# 2016.net
KiCad netlist of a schematic drawn in Altium Designer
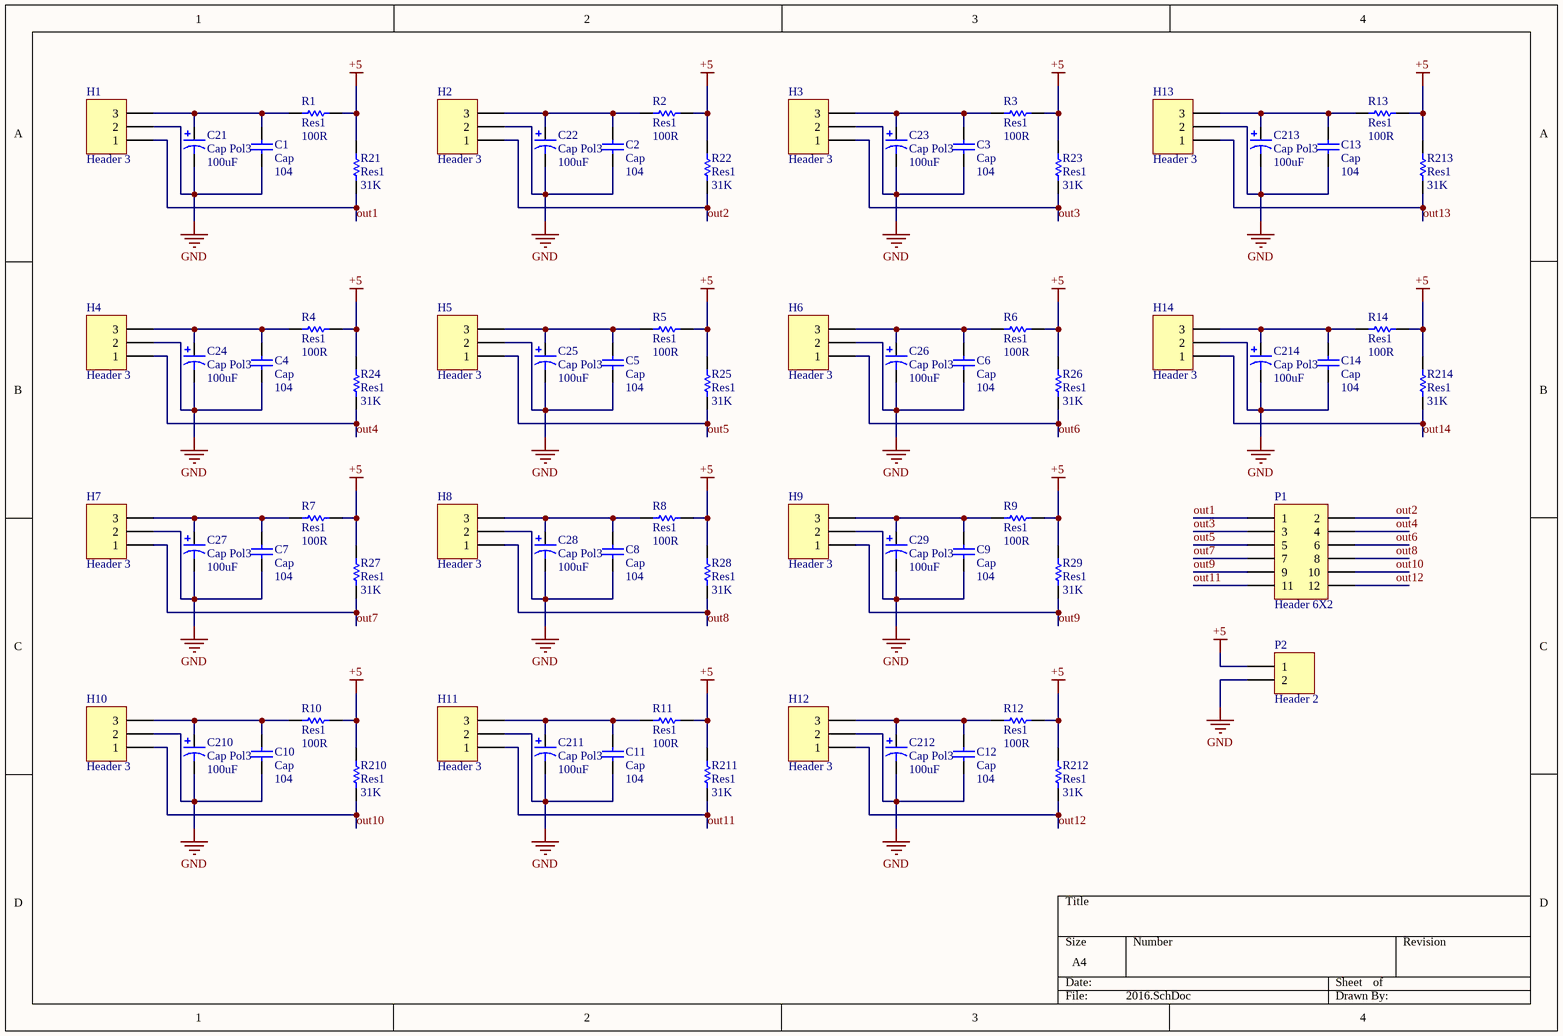
[diagram p0: 2016.SchDoc]

(export (version "E")
  (design (tool "Eeschema 10.0.6"))
  (components
    (comp (ref "C1")
      (value "Cap")
      (footprint "0805C")
      (description "Capacitor")
      (fields (field (name "ALTIUM_VALUE") "104") (field (name "PUBLISHER") "Altium Limited"))
      (libsource (lib "Miscellaneous Devices") (part "Cap"))
    )
    (comp (ref "C2")
      (value "Cap")
      (footprint "0805C")
      (description "Capacitor")
      (fields (field (name "ALTIUM_VALUE") "104") (field (name "PUBLISHER") "Altium Limited"))
      (libsource (lib "Miscellaneous Devices") (part "Cap"))
    )
    (comp (ref "C3")
      (value "Cap")
      (footprint "0805C")
      (description "Capacitor")
      (fields (field (name "ALTIUM_VALUE") "104") (field (name "PUBLISHER") "Altium Limited"))
      (libsource (lib "Miscellaneous Devices") (part "Cap"))
    )
    (comp (ref "C4")
      (value "Cap")
      (footprint "0805C")
      (description "Capacitor")
      (fields (field (name "ALTIUM_VALUE") "104") (field (name "PUBLISHER") "Altium Limited"))
      (libsource (lib "Miscellaneous Devices") (part "Cap"))
    )
    (comp (ref "C5")
      (value "Cap")
      (footprint "0805C")
      (description "Capacitor")
      (fields (field (name "ALTIUM_VALUE") "104") (field (name "PUBLISHER") "Altium Limited"))
      (libsource (lib "Miscellaneous Devices") (part "Cap"))
    )
    (comp (ref "C6")
      (value "Cap")
      (footprint "0805C")
      (description "Capacitor")
      (fields (field (name "ALTIUM_VALUE") "104") (field (name "PUBLISHER") "Altium Limited"))
      (libsource (lib "Miscellaneous Devices") (part "Cap"))
    )
    (comp (ref "C7")
      (value "Cap")
      (footprint "0805C")
      (description "Capacitor")
      (fields (field (name "ALTIUM_VALUE") "104") (field (name "PUBLISHER") "Altium Limited"))
      (libsource (lib "Miscellaneous Devices") (part "Cap"))
    )
    (comp (ref "C8")
      (value "Cap")
      (footprint "0805C")
      (description "Capacitor")
      (fields (field (name "ALTIUM_VALUE") "104") (field (name "PUBLISHER") "Altium Limited"))
      (libsource (lib "Miscellaneous Devices") (part "Cap"))
    )
    (comp (ref "C9")
      (value "Cap")
      (footprint "0805C")
      (description "Capacitor")
      (fields (field (name "ALTIUM_VALUE") "104") (field (name "PUBLISHER") "Altium Limited"))
      (libsource (lib "Miscellaneous Devices") (part "Cap"))
    )
    (comp (ref "C10")
      (value "Cap")
      (footprint "0805C")
      (description "Capacitor")
      (fields (field (name "ALTIUM_VALUE") "104") (field (name "PUBLISHER") "Altium Limited"))
      (libsource (lib "Miscellaneous Devices") (part "Cap"))
    )
    (comp (ref "C11")
      (value "Cap")
      (footprint "0805C")
      (description "Capacitor")
      (fields (field (name "ALTIUM_VALUE") "104") (field (name "PUBLISHER") "Altium Limited"))
      (libsource (lib "Miscellaneous Devices") (part "Cap"))
    )
    (comp (ref "C12")
      (value "Cap")
      (footprint "0805C")
      (description "Capacitor")
      (fields (field (name "ALTIUM_VALUE") "104") (field (name "PUBLISHER") "Altium Limited"))
      (libsource (lib "Miscellaneous Devices") (part "Cap"))
    )
    (comp (ref "C13")
      (value "Cap")
      (footprint "0805C")
      (description "Capacitor")
      (fields (field (name "ALTIUM_VALUE") "104") (field (name "PUBLISHER") "Altium Limited"))
      (libsource (lib "Miscellaneous Devices") (part "Cap"))
    )
    (comp (ref "C14")
      (value "Cap")
      (footprint "0805C")
      (description "Capacitor")
      (fields (field (name "ALTIUM_VALUE") "104") (field (name "PUBLISHER") "Altium Limited"))
      (libsource (lib "Miscellaneous Devices") (part "Cap"))
    )
    (comp (ref "C21")
      (value "Cap Pol3")
      (footprint "0805C")
      (description "Polarized Capacitor (Surface Mount)")
      (fields (field (name "ALTIUM_VALUE") "100uF") (field (name "PUBLISHER") "Altium Limited"))
      (libsource (lib "Miscellaneous Devices") (part "Cap Pol3"))
    )
    (comp (ref "C22")
      (value "Cap Pol3")
      (footprint "0805C")
      (description "Polarized Capacitor (Surface Mount)")
      (fields (field (name "ALTIUM_VALUE") "100uF") (field (name "PUBLISHER") "Altium Limited"))
      (libsource (lib "Miscellaneous Devices") (part "Cap Pol3"))
    )
    (comp (ref "C23")
      (value "Cap Pol3")
      (footprint "0805C")
      (description "Polarized Capacitor (Surface Mount)")
      (fields (field (name "ALTIUM_VALUE") "100uF") (field (name "PUBLISHER") "Altium Limited"))
      (libsource (lib "Miscellaneous Devices") (part "Cap Pol3"))
    )
    (comp (ref "C24")
      (value "Cap Pol3")
      (footprint "0805C")
      (description "Polarized Capacitor (Surface Mount)")
      (fields (field (name "ALTIUM_VALUE") "100uF") (field (name "PUBLISHER") "Altium Limited"))
      (libsource (lib "Miscellaneous Devices") (part "Cap Pol3"))
    )
    (comp (ref "C25")
      (value "Cap Pol3")
      (footprint "0805C")
      (description "Polarized Capacitor (Surface Mount)")
      (fields (field (name "ALTIUM_VALUE") "100uF") (field (name "PUBLISHER") "Altium Limited"))
      (libsource (lib "Miscellaneous Devices") (part "Cap Pol3"))
    )
    (comp (ref "C26")
      (value "Cap Pol3")
      (footprint "0805C")
      (description "Polarized Capacitor (Surface Mount)")
      (fields (field (name "ALTIUM_VALUE") "100uF") (field (name "PUBLISHER") "Altium Limited"))
      (libsource (lib "Miscellaneous Devices") (part "Cap Pol3"))
    )
    (comp (ref "C27")
      (value "Cap Pol3")
      (footprint "0805C")
      (description "Polarized Capacitor (Surface Mount)")
      (fields (field (name "ALTIUM_VALUE") "100uF") (field (name "PUBLISHER") "Altium Limited"))
      (libsource (lib "Miscellaneous Devices") (part "Cap Pol3"))
    )
    (comp (ref "C28")
      (value "Cap Pol3")
      (footprint "0805C")
      (description "Polarized Capacitor (Surface Mount)")
      (fields (field (name "ALTIUM_VALUE") "100uF") (field (name "PUBLISHER") "Altium Limited"))
      (libsource (lib "Miscellaneous Devices") (part "Cap Pol3"))
    )
    (comp (ref "C29")
      (value "Cap Pol3")
      (footprint "0805C")
      (description "Polarized Capacitor (Surface Mount)")
      (fields (field (name "ALTIUM_VALUE") "100uF") (field (name "PUBLISHER") "Altium Limited"))
      (libsource (lib "Miscellaneous Devices") (part "Cap Pol3"))
    )
    (comp (ref "C210")
      (value "Cap Pol3")
      (footprint "0805C")
      (description "Polarized Capacitor (Surface Mount)")
      (fields (field (name "ALTIUM_VALUE") "100uF") (field (name "PUBLISHER") "Altium Limited"))
      (libsource (lib "Miscellaneous Devices") (part "Cap Pol3"))
    )
    (comp (ref "C211")
      (value "Cap Pol3")
      (footprint "0805C")
      (description "Polarized Capacitor (Surface Mount)")
      (fields (field (name "ALTIUM_VALUE") "100uF") (field (name "PUBLISHER") "Altium Limited"))
      (libsource (lib "Miscellaneous Devices") (part "Cap Pol3"))
    )
    (comp (ref "C212")
      (value "Cap Pol3")
      (footprint "0805C")
      (description "Polarized Capacitor (Surface Mount)")
      (fields (field (name "ALTIUM_VALUE") "100uF") (field (name "PUBLISHER") "Altium Limited"))
      (libsource (lib "Miscellaneous Devices") (part "Cap Pol3"))
    )
    (comp (ref "C213")
      (value "Cap Pol3")
      (footprint "0805C")
      (description "Polarized Capacitor (Surface Mount)")
      (fields (field (name "ALTIUM_VALUE") "100uF") (field (name "PUBLISHER") "Altium Limited"))
      (libsource (lib "Miscellaneous Devices") (part "Cap Pol3"))
    )
    (comp (ref "C214")
      (value "Cap Pol3")
      (footprint "0805C")
      (description "Polarized Capacitor (Surface Mount)")
      (fields (field (name "ALTIUM_VALUE") "100uF") (field (name "PUBLISHER") "Altium Limited"))
      (libsource (lib "Miscellaneous Devices") (part "Cap Pol3"))
    )
    (comp (ref "H1")
      (value "Header 3")
      (footprint "HDR1X3")
      (description "Header, 3-Pin")
      (fields (field (name "PUBLISHER") "Altium Limited"))
      (libsource (lib "Miscellaneous Connectors") (part "Header 3"))
    )
    (comp (ref "H2")
      (value "Header 3")
      (footprint "HDR1X3")
      (description "Header, 3-Pin")
      (fields (field (name "PUBLISHER") "Altium Limited"))
      (libsource (lib "Miscellaneous Connectors") (part "Header 3"))
    )
    (comp (ref "H3")
      (value "Header 3")
      (footprint "HDR1X3")
      (description "Header, 3-Pin")
      (fields (field (name "PUBLISHER") "Altium Limited"))
      (libsource (lib "Miscellaneous Connectors") (part "Header 3"))
    )
    (comp (ref "H4")
      (value "Header 3")
      (footprint "HDR1X3")
      (description "Header, 3-Pin")
      (fields (field (name "PUBLISHER") "Altium Limited"))
      (libsource (lib "Miscellaneous Connectors") (part "Header 3"))
    )
    (comp (ref "H5")
      (value "Header 3")
      (footprint "HDR1X3")
      (description "Header, 3-Pin")
      (fields (field (name "PUBLISHER") "Altium Limited"))
      (libsource (lib "Miscellaneous Connectors") (part "Header 3"))
    )
    (comp (ref "H6")
      (value "Header 3")
      (footprint "HDR1X3")
      (description "Header, 3-Pin")
      (fields (field (name "PUBLISHER") "Altium Limited"))
      (libsource (lib "Miscellaneous Connectors") (part "Header 3"))
    )
    (comp (ref "H7")
      (value "Header 3")
      (footprint "HDR1X3")
      (description "Header, 3-Pin")
      (fields (field (name "PUBLISHER") "Altium Limited"))
      (libsource (lib "Miscellaneous Connectors") (part "Header 3"))
    )
    (comp (ref "H8")
      (value "Header 3")
      (footprint "HDR1X3")
      (description "Header, 3-Pin")
      (fields (field (name "PUBLISHER") "Altium Limited"))
      (libsource (lib "Miscellaneous Connectors") (part "Header 3"))
    )
    (comp (ref "H9")
      (value "Header 3")
      (footprint "HDR1X3")
      (description "Header, 3-Pin")
      (fields (field (name "PUBLISHER") "Altium Limited"))
      (libsource (lib "Miscellaneous Connectors") (part "Header 3"))
    )
    (comp (ref "H10")
      (value "Header 3")
      (footprint "HDR1X3")
      (description "Header, 3-Pin")
      (fields (field (name "PUBLISHER") "Altium Limited"))
      (libsource (lib "Miscellaneous Connectors") (part "Header 3"))
    )
    (comp (ref "H11")
      (value "Header 3")
      (footprint "HDR1X3")
      (description "Header, 3-Pin")
      (fields (field (name "PUBLISHER") "Altium Limited"))
      (libsource (lib "Miscellaneous Connectors") (part "Header 3"))
    )
    (comp (ref "H12")
      (value "Header 3")
      (footprint "HDR1X3")
      (description "Header, 3-Pin")
      (fields (field (name "PUBLISHER") "Altium Limited"))
      (libsource (lib "Miscellaneous Connectors") (part "Header 3"))
    )
    (comp (ref "H13")
      (value "Header 3")
      (footprint "HDR1X3")
      (description "Header, 3-Pin")
      (fields (field (name "PUBLISHER") "Altium Limited"))
      (libsource (lib "Miscellaneous Connectors") (part "Header 3"))
    )
    (comp (ref "H14")
      (value "Header 3")
      (footprint "HDR1X3")
      (description "Header, 3-Pin")
      (fields (field (name "PUBLISHER") "Altium Limited"))
      (libsource (lib "Miscellaneous Connectors") (part "Header 3"))
    )
    (comp (ref "P1")
      (value "Header 6X2")
      (footprint "HDR2X6")
      (description "Header, 6-Pin, Dual row")
      (fields (field (name "PUBLISHER") "Altium Limited"))
      (libsource (lib "Miscellaneous Connectors") (part "Header 6X2"))
    )
    (comp (ref "P2")
      (value "Header 2")
      (footprint "HDR1X2")
      (description "Header, 2-Pin")
      (fields (field (name "PUBLISHER") "Altium Limited"))
      (libsource (lib "Miscellaneous Connectors") (part "Header 2"))
    )
    (comp (ref "R1")
      (value "Res1")
      (footprint "0805R")
      (description "Resistor")
      (fields (field (name "ALTIUM_VALUE") "100R") (field (name "PUBLISHER") "Altium Limited"))
      (libsource (lib "Miscellaneous Devices") (part "Res1"))
    )
    (comp (ref "R2")
      (value "Res1")
      (footprint "0805R")
      (description "Resistor")
      (fields (field (name "ALTIUM_VALUE") "100R") (field (name "PUBLISHER") "Altium Limited"))
      (libsource (lib "Miscellaneous Devices") (part "Res1"))
    )
    (comp (ref "R3")
      (value "Res1")
      (footprint "0805R")
      (description "Resistor")
      (fields (field (name "ALTIUM_VALUE") "100R") (field (name "PUBLISHER") "Altium Limited"))
      (libsource (lib "Miscellaneous Devices") (part "Res1"))
    )
    (comp (ref "R4")
      (value "Res1")
      (footprint "0805R")
      (description "Resistor")
      (fields (field (name "ALTIUM_VALUE") "100R") (field (name "PUBLISHER") "Altium Limited"))
      (libsource (lib "Miscellaneous Devices") (part "Res1"))
    )
    (comp (ref "R5")
      (value "Res1")
      (footprint "0805R")
      (description "Resistor")
      (fields (field (name "ALTIUM_VALUE") "100R") (field (name "PUBLISHER") "Altium Limited"))
      (libsource (lib "Miscellaneous Devices") (part "Res1"))
    )
    (comp (ref "R6")
      (value "Res1")
      (footprint "0805R")
      (description "Resistor")
      (fields (field (name "ALTIUM_VALUE") "100R") (field (name "PUBLISHER") "Altium Limited"))
      (libsource (lib "Miscellaneous Devices") (part "Res1"))
    )
    (comp (ref "R7")
      (value "Res1")
      (footprint "0805R")
      (description "Resistor")
      (fields (field (name "ALTIUM_VALUE") "100R") (field (name "PUBLISHER") "Altium Limited"))
      (libsource (lib "Miscellaneous Devices") (part "Res1"))
    )
    (comp (ref "R8")
      (value "Res1")
      (footprint "0805R")
      (description "Resistor")
      (fields (field (name "ALTIUM_VALUE") "100R") (field (name "PUBLISHER") "Altium Limited"))
      (libsource (lib "Miscellaneous Devices") (part "Res1"))
    )
    (comp (ref "R9")
      (value "Res1")
      (footprint "0805R")
      (description "Resistor")
      (fields (field (name "ALTIUM_VALUE") "100R") (field (name "PUBLISHER") "Altium Limited"))
      (libsource (lib "Miscellaneous Devices") (part "Res1"))
    )
    (comp (ref "R10")
      (value "Res1")
      (footprint "0805R")
      (description "Resistor")
      (fields (field (name "ALTIUM_VALUE") "100R") (field (name "PUBLISHER") "Altium Limited"))
      (libsource (lib "Miscellaneous Devices") (part "Res1"))
    )
    (comp (ref "R11")
      (value "Res1")
      (footprint "0805R")
      (description "Resistor")
      (fields (field (name "ALTIUM_VALUE") "100R") (field (name "PUBLISHER") "Altium Limited"))
      (libsource (lib "Miscellaneous Devices") (part "Res1"))
    )
    (comp (ref "R12")
      (value "Res1")
      (footprint "0805R")
      (description "Resistor")
      (fields (field (name "ALTIUM_VALUE") "100R") (field (name "PUBLISHER") "Altium Limited"))
      (libsource (lib "Miscellaneous Devices") (part "Res1"))
    )
    (comp (ref "R13")
      (value "Res1")
      (footprint "0805R")
      (description "Resistor")
      (fields (field (name "ALTIUM_VALUE") "100R") (field (name "PUBLISHER") "Altium Limited"))
      (libsource (lib "Miscellaneous Devices") (part "Res1"))
    )
    (comp (ref "R14")
      (value "Res1")
      (footprint "0805R")
      (description "Resistor")
      (fields (field (name "ALTIUM_VALUE") "100R") (field (name "PUBLISHER") "Altium Limited"))
      (libsource (lib "Miscellaneous Devices") (part "Res1"))
    )
    (comp (ref "R21")
      (value "Res1")
      (footprint "0805R")
      (description "Resistor")
      (fields (field (name "ALTIUM_VALUE") "31K") (field (name "PUBLISHER") "Altium Limited"))
      (libsource (lib "Miscellaneous Devices") (part "Res1"))
    )
    (comp (ref "R22")
      (value "Res1")
      (footprint "0805R")
      (description "Resistor")
      (fields (field (name "ALTIUM_VALUE") "31K") (field (name "PUBLISHER") "Altium Limited"))
      (libsource (lib "Miscellaneous Devices") (part "Res1"))
    )
    (comp (ref "R23")
      (value "Res1")
      (footprint "0805R")
      (description "Resistor")
      (fields (field (name "ALTIUM_VALUE") "31K") (field (name "PUBLISHER") "Altium Limited"))
      (libsource (lib "Miscellaneous Devices") (part "Res1"))
    )
    (comp (ref "R24")
      (value "Res1")
      (footprint "0805R")
      (description "Resistor")
      (fields (field (name "ALTIUM_VALUE") "31K") (field (name "PUBLISHER") "Altium Limited"))
      (libsource (lib "Miscellaneous Devices") (part "Res1"))
    )
    (comp (ref "R25")
      (value "Res1")
      (footprint "0805R")
      (description "Resistor")
      (fields (field (name "ALTIUM_VALUE") "31K") (field (name "PUBLISHER") "Altium Limited"))
      (libsource (lib "Miscellaneous Devices") (part "Res1"))
    )
    (comp (ref "R26")
      (value "Res1")
      (footprint "0805R")
      (description "Resistor")
      (fields (field (name "ALTIUM_VALUE") "31K") (field (name "PUBLISHER") "Altium Limited"))
      (libsource (lib "Miscellaneous Devices") (part "Res1"))
    )
    (comp (ref "R27")
      (value "Res1")
      (footprint "0805R")
      (description "Resistor")
      (fields (field (name "ALTIUM_VALUE") "31K") (field (name "PUBLISHER") "Altium Limited"))
      (libsource (lib "Miscellaneous Devices") (part "Res1"))
    )
    (comp (ref "R28")
      (value "Res1")
      (footprint "0805R")
      (description "Resistor")
      (fields (field (name "ALTIUM_VALUE") "31K") (field (name "PUBLISHER") "Altium Limited"))
      (libsource (lib "Miscellaneous Devices") (part "Res1"))
    )
    (comp (ref "R29")
      (value "Res1")
      (footprint "0805R")
      (description "Resistor")
      (fields (field (name "ALTIUM_VALUE") "31K") (field (name "PUBLISHER") "Altium Limited"))
      (libsource (lib "Miscellaneous Devices") (part "Res1"))
    )
    (comp (ref "R210")
      (value "Res1")
      (footprint "0805R")
      (description "Resistor")
      (fields (field (name "ALTIUM_VALUE") "31K") (field (name "PUBLISHER") "Altium Limited"))
      (libsource (lib "Miscellaneous Devices") (part "Res1"))
    )
    (comp (ref "R211")
      (value "Res1")
      (footprint "0805R")
      (description "Resistor")
      (fields (field (name "ALTIUM_VALUE") "31K") (field (name "PUBLISHER") "Altium Limited"))
      (libsource (lib "Miscellaneous Devices") (part "Res1"))
    )
    (comp (ref "R212")
      (value "Res1")
      (footprint "0805R")
      (description "Resistor")
      (fields (field (name "ALTIUM_VALUE") "31K") (field (name "PUBLISHER") "Altium Limited"))
      (libsource (lib "Miscellaneous Devices") (part "Res1"))
    )
    (comp (ref "R213")
      (value "Res1")
      (footprint "0805R")
      (description "Resistor")
      (fields (field (name "ALTIUM_VALUE") "31K") (field (name "PUBLISHER") "Altium Limited"))
      (libsource (lib "Miscellaneous Devices") (part "Res1"))
    )
    (comp (ref "R214")
      (value "Res1")
      (footprint "0805R")
      (description "Resistor")
      (fields (field (name "ALTIUM_VALUE") "31K") (field (name "PUBLISHER") "Altium Limited"))
      (libsource (lib "Miscellaneous Devices") (part "Res1"))
    )
  )
  (nets
    (net (code "1") (name "+5") (class "Default")
      (node (ref "P2") (pin "1") (pinfunction "1_1") (pintype "passive"))
      (node (ref "R1") (pin "2") (pinfunction "2_2") (pintype "passive"))
      (node (ref "R10") (pin "2") (pinfunction "2_2") (pintype "passive"))
      (node (ref "R11") (pin "2") (pinfunction "2_2") (pintype "passive"))
      (node (ref "R12") (pin "2") (pinfunction "2_2") (pintype "passive"))
      (node (ref "R13") (pin "2") (pinfunction "2_2") (pintype "passive"))
      (node (ref "R14") (pin "2") (pinfunction "2_2") (pintype "passive"))
      (node (ref "R2") (pin "2") (pinfunction "2_2") (pintype "passive"))
      (node (ref "R21") (pin "2") (pinfunction "2_2") (pintype "passive"))
      (node (ref "R210") (pin "2") (pinfunction "2_2") (pintype "passive"))
      (node (ref "R211") (pin "2") (pinfunction "2_2") (pintype "passive"))
      (node (ref "R212") (pin "2") (pinfunction "2_2") (pintype "passive"))
      (node (ref "R213") (pin "2") (pinfunction "2_2") (pintype "passive"))
      (node (ref "R214") (pin "2") (pinfunction "2_2") (pintype "passive"))
      (node (ref "R22") (pin "2") (pinfunction "2_2") (pintype "passive"))
      (node (ref "R23") (pin "2") (pinfunction "2_2") (pintype "passive"))
      (node (ref "R24") (pin "2") (pinfunction "2_2") (pintype "passive"))
      (node (ref "R25") (pin "2") (pinfunction "2_2") (pintype "passive"))
      (node (ref "R26") (pin "2") (pinfunction "2_2") (pintype "passive"))
      (node (ref "R27") (pin "2") (pinfunction "2_2") (pintype "passive"))
      (node (ref "R28") (pin "2") (pinfunction "2_2") (pintype "passive"))
      (node (ref "R29") (pin "2") (pinfunction "2_2") (pintype "passive"))
      (node (ref "R3") (pin "2") (pinfunction "2_2") (pintype "passive"))
      (node (ref "R4") (pin "2") (pinfunction "2_2") (pintype "passive"))
      (node (ref "R5") (pin "2") (pinfunction "2_2") (pintype "passive"))
      (node (ref "R6") (pin "2") (pinfunction "2_2") (pintype "passive"))
      (node (ref "R7") (pin "2") (pinfunction "2_2") (pintype "passive"))
      (node (ref "R8") (pin "2") (pinfunction "2_2") (pintype "passive"))
      (node (ref "R9") (pin "2") (pinfunction "2_2") (pintype "passive"))
    )
    (net (code "2") (name "/out1") (class "Default")
      (node (ref "H1") (pin "1") (pinfunction "1_1") (pintype "passive"))
      (node (ref "P1") (pin "1") (pinfunction "1_1") (pintype "passive"))
      (node (ref "R21") (pin "1") (pinfunction "1_1") (pintype "passive"))
    )
    (net (code "3") (name "/out2") (class "Default")
      (node (ref "H2") (pin "1") (pinfunction "1_1") (pintype "passive"))
      (node (ref "P1") (pin "2") (pinfunction "2_2") (pintype "passive"))
      (node (ref "R22") (pin "1") (pinfunction "1_1") (pintype "passive"))
    )
    (net (code "4") (name "/out3") (class "Default")
      (node (ref "H3") (pin "1") (pinfunction "1_1") (pintype "passive"))
      (node (ref "P1") (pin "3") (pinfunction "3_3") (pintype "passive"))
      (node (ref "R23") (pin "1") (pinfunction "1_1") (pintype "passive"))
    )
    (net (code "5") (name "/out4") (class "Default")
      (node (ref "H4") (pin "1") (pinfunction "1_1") (pintype "passive"))
      (node (ref "P1") (pin "4") (pinfunction "4_4") (pintype "passive"))
      (node (ref "R24") (pin "1") (pinfunction "1_1") (pintype "passive"))
    )
    (net (code "6") (name "/out5") (class "Default")
      (node (ref "H5") (pin "1") (pinfunction "1_1") (pintype "passive"))
      (node (ref "P1") (pin "5") (pinfunction "5_5") (pintype "passive"))
      (node (ref "R25") (pin "1") (pinfunction "1_1") (pintype "passive"))
    )
    (net (code "7") (name "/out6") (class "Default")
      (node (ref "H6") (pin "1") (pinfunction "1_1") (pintype "passive"))
      (node (ref "P1") (pin "6") (pinfunction "6_6") (pintype "passive"))
      (node (ref "R26") (pin "1") (pinfunction "1_1") (pintype "passive"))
    )
    (net (code "8") (name "/out7") (class "Default")
      (node (ref "H7") (pin "1") (pinfunction "1_1") (pintype "passive"))
      (node (ref "P1") (pin "7") (pinfunction "7_7") (pintype "passive"))
      (node (ref "R27") (pin "1") (pinfunction "1_1") (pintype "passive"))
    )
    (net (code "9") (name "/out8") (class "Default")
      (node (ref "H8") (pin "1") (pinfunction "1_1") (pintype "passive"))
      (node (ref "P1") (pin "8") (pinfunction "8_8") (pintype "passive"))
      (node (ref "R28") (pin "1") (pinfunction "1_1") (pintype "passive"))
    )
    (net (code "10") (name "/out9") (class "Default")
      (node (ref "H9") (pin "1") (pinfunction "1_1") (pintype "passive"))
      (node (ref "P1") (pin "9") (pinfunction "9_9") (pintype "passive"))
      (node (ref "R29") (pin "1") (pinfunction "1_1") (pintype "passive"))
    )
    (net (code "11") (name "/out10") (class "Default")
      (node (ref "H10") (pin "1") (pinfunction "1_1") (pintype "passive"))
      (node (ref "P1") (pin "10") (pinfunction "10_10") (pintype "passive"))
      (node (ref "R210") (pin "1") (pinfunction "1_1") (pintype "passive"))
    )
    (net (code "12") (name "/out11") (class "Default")
      (node (ref "H11") (pin "1") (pinfunction "1_1") (pintype "passive"))
      (node (ref "P1") (pin "11") (pinfunction "11_11") (pintype "passive"))
      (node (ref "R211") (pin "1") (pinfunction "1_1") (pintype "passive"))
    )
    (net (code "13") (name "/out12") (class "Default")
      (node (ref "H12") (pin "1") (pinfunction "1_1") (pintype "passive"))
      (node (ref "P1") (pin "12") (pinfunction "12_12") (pintype "passive"))
      (node (ref "R212") (pin "1") (pinfunction "1_1") (pintype "passive"))
    )
    (net (code "14") (name "/out13") (class "Default")
      (node (ref "H13") (pin "1") (pinfunction "1_1") (pintype "passive"))
      (node (ref "R213") (pin "1") (pinfunction "1_1") (pintype "passive"))
    )
    (net (code "15") (name "/out14") (class "Default")
      (node (ref "H14") (pin "1") (pinfunction "1_1") (pintype "passive"))
      (node (ref "R214") (pin "1") (pinfunction "1_1") (pintype "passive"))
    )
    (net (code "16") (name "GND") (class "Default")
      (node (ref "C1") (pin "1") (pinfunction "1_1") (pintype "passive"))
      (node (ref "C10") (pin "1") (pinfunction "1_1") (pintype "passive"))
      (node (ref "C11") (pin "1") (pinfunction "1_1") (pintype "passive"))
      (node (ref "C12") (pin "1") (pinfunction "1_1") (pintype "passive"))
      (node (ref "C13") (pin "1") (pinfunction "1_1") (pintype "passive"))
      (node (ref "C14") (pin "1") (pinfunction "1_1") (pintype "passive"))
      (node (ref "C2") (pin "1") (pinfunction "1_1") (pintype "passive"))
      (node (ref "C21") (pin "2") (pinfunction "2_2") (pintype "passive"))
      (node (ref "C210") (pin "2") (pinfunction "2_2") (pintype "passive"))
      (node (ref "C211") (pin "2") (pinfunction "2_2") (pintype "passive"))
      (node (ref "C212") (pin "2") (pinfunction "2_2") (pintype "passive"))
      (node (ref "C213") (pin "2") (pinfunction "2_2") (pintype "passive"))
      (node (ref "C214") (pin "2") (pinfunction "2_2") (pintype "passive"))
      (node (ref "C22") (pin "2") (pinfunction "2_2") (pintype "passive"))
      (node (ref "C23") (pin "2") (pinfunction "2_2") (pintype "passive"))
      (node (ref "C24") (pin "2") (pinfunction "2_2") (pintype "passive"))
      (node (ref "C25") (pin "2") (pinfunction "2_2") (pintype "passive"))
      (node (ref "C26") (pin "2") (pinfunction "2_2") (pintype "passive"))
      (node (ref "C27") (pin "2") (pinfunction "2_2") (pintype "passive"))
      (node (ref "C28") (pin "2") (pinfunction "2_2") (pintype "passive"))
      (node (ref "C29") (pin "2") (pinfunction "2_2") (pintype "passive"))
      (node (ref "C3") (pin "1") (pinfunction "1_1") (pintype "passive"))
      (node (ref "C4") (pin "1") (pinfunction "1_1") (pintype "passive"))
      (node (ref "C5") (pin "1") (pinfunction "1_1") (pintype "passive"))
      (node (ref "C6") (pin "1") (pinfunction "1_1") (pintype "passive"))
      (node (ref "C7") (pin "1") (pinfunction "1_1") (pintype "passive"))
      (node (ref "C8") (pin "1") (pinfunction "1_1") (pintype "passive"))
      (node (ref "C9") (pin "1") (pinfunction "1_1") (pintype "passive"))
      (node (ref "H1") (pin "2") (pinfunction "2_2") (pintype "passive"))
      (node (ref "H10") (pin "2") (pinfunction "2_2") (pintype "passive"))
      (node (ref "H11") (pin "2") (pinfunction "2_2") (pintype "passive"))
      (node (ref "H12") (pin "2") (pinfunction "2_2") (pintype "passive"))
      (node (ref "H13") (pin "2") (pinfunction "2_2") (pintype "passive"))
      (node (ref "H14") (pin "2") (pinfunction "2_2") (pintype "passive"))
      (node (ref "H2") (pin "2") (pinfunction "2_2") (pintype "passive"))
      (node (ref "H3") (pin "2") (pinfunction "2_2") (pintype "passive"))
      (node (ref "H4") (pin "2") (pinfunction "2_2") (pintype "passive"))
      (node (ref "H5") (pin "2") (pinfunction "2_2") (pintype "passive"))
      (node (ref "H6") (pin "2") (pinfunction "2_2") (pintype "passive"))
      (node (ref "H7") (pin "2") (pinfunction "2_2") (pintype "passive"))
      (node (ref "H8") (pin "2") (pinfunction "2_2") (pintype "passive"))
      (node (ref "H9") (pin "2") (pinfunction "2_2") (pintype "passive"))
      (node (ref "P2") (pin "2") (pinfunction "2_2") (pintype "passive"))
    )
    (net (code "17") (name "Net-(C1-Pad2)") (class "Default")
      (node (ref "C1") (pin "2") (pinfunction "2_2") (pintype "passive"))
      (node (ref "C21") (pin "1") (pinfunction "1_1") (pintype "passive"))
      (node (ref "H1") (pin "3") (pinfunction "3_3") (pintype "passive"))
      (node (ref "R1") (pin "1") (pinfunction "1_1") (pintype "passive"))
    )
    (net (code "18") (name "Net-(C2-Pad2)") (class "Default")
      (node (ref "C2") (pin "2") (pinfunction "2_2") (pintype "passive"))
      (node (ref "C22") (pin "1") (pinfunction "1_1") (pintype "passive"))
      (node (ref "H2") (pin "3") (pinfunction "3_3") (pintype "passive"))
      (node (ref "R2") (pin "1") (pinfunction "1_1") (pintype "passive"))
    )
    (net (code "19") (name "Net-(C10-Pad2)") (class "Default")
      (node (ref "C10") (pin "2") (pinfunction "2_2") (pintype "passive"))
      (node (ref "C210") (pin "1") (pinfunction "1_1") (pintype "passive"))
      (node (ref "H10") (pin "3") (pinfunction "3_3") (pintype "passive"))
      (node (ref "R10") (pin "1") (pinfunction "1_1") (pintype "passive"))
    )
    (net (code "20") (name "Net-(C11-Pad2)") (class "Default")
      (node (ref "C11") (pin "2") (pinfunction "2_2") (pintype "passive"))
      (node (ref "C211") (pin "1") (pinfunction "1_1") (pintype "passive"))
      (node (ref "H11") (pin "3") (pinfunction "3_3") (pintype "passive"))
      (node (ref "R11") (pin "1") (pinfunction "1_1") (pintype "passive"))
    )
    (net (code "21") (name "Net-(C12-Pad2)") (class "Default")
      (node (ref "C12") (pin "2") (pinfunction "2_2") (pintype "passive"))
      (node (ref "C212") (pin "1") (pinfunction "1_1") (pintype "passive"))
      (node (ref "H12") (pin "3") (pinfunction "3_3") (pintype "passive"))
      (node (ref "R12") (pin "1") (pinfunction "1_1") (pintype "passive"))
    )
    (net (code "22") (name "Net-(C13-Pad2)") (class "Default")
      (node (ref "C13") (pin "2") (pinfunction "2_2") (pintype "passive"))
      (node (ref "C213") (pin "1") (pinfunction "1_1") (pintype "passive"))
      (node (ref "H13") (pin "3") (pinfunction "3_3") (pintype "passive"))
      (node (ref "R13") (pin "1") (pinfunction "1_1") (pintype "passive"))
    )
    (net (code "23") (name "Net-(C14-Pad2)") (class "Default")
      (node (ref "C14") (pin "2") (pinfunction "2_2") (pintype "passive"))
      (node (ref "C214") (pin "1") (pinfunction "1_1") (pintype "passive"))
      (node (ref "H14") (pin "3") (pinfunction "3_3") (pintype "passive"))
      (node (ref "R14") (pin "1") (pinfunction "1_1") (pintype "passive"))
    )
    (net (code "24") (name "Net-(C23-Pad1)") (class "Default")
      (node (ref "C23") (pin "1") (pinfunction "1_1") (pintype "passive"))
      (node (ref "C3") (pin "2") (pinfunction "2_2") (pintype "passive"))
      (node (ref "H3") (pin "3") (pinfunction "3_3") (pintype "passive"))
      (node (ref "R3") (pin "1") (pinfunction "1_1") (pintype "passive"))
    )
    (net (code "25") (name "Net-(C24-Pad1)") (class "Default")
      (node (ref "C24") (pin "1") (pinfunction "1_1") (pintype "passive"))
      (node (ref "C4") (pin "2") (pinfunction "2_2") (pintype "passive"))
      (node (ref "H4") (pin "3") (pinfunction "3_3") (pintype "passive"))
      (node (ref "R4") (pin "1") (pinfunction "1_1") (pintype "passive"))
    )
    (net (code "26") (name "Net-(C25-Pad1)") (class "Default")
      (node (ref "C25") (pin "1") (pinfunction "1_1") (pintype "passive"))
      (node (ref "C5") (pin "2") (pinfunction "2_2") (pintype "passive"))
      (node (ref "H5") (pin "3") (pinfunction "3_3") (pintype "passive"))
      (node (ref "R5") (pin "1") (pinfunction "1_1") (pintype "passive"))
    )
    (net (code "27") (name "Net-(C26-Pad1)") (class "Default")
      (node (ref "C26") (pin "1") (pinfunction "1_1") (pintype "passive"))
      (node (ref "C6") (pin "2") (pinfunction "2_2") (pintype "passive"))
      (node (ref "H6") (pin "3") (pinfunction "3_3") (pintype "passive"))
      (node (ref "R6") (pin "1") (pinfunction "1_1") (pintype "passive"))
    )
    (net (code "28") (name "Net-(C27-Pad1)") (class "Default")
      (node (ref "C27") (pin "1") (pinfunction "1_1") (pintype "passive"))
      (node (ref "C7") (pin "2") (pinfunction "2_2") (pintype "passive"))
      (node (ref "H7") (pin "3") (pinfunction "3_3") (pintype "passive"))
      (node (ref "R7") (pin "1") (pinfunction "1_1") (pintype "passive"))
    )
    (net (code "29") (name "Net-(C28-Pad1)") (class "Default")
      (node (ref "C28") (pin "1") (pinfunction "1_1") (pintype "passive"))
      (node (ref "C8") (pin "2") (pinfunction "2_2") (pintype "passive"))
      (node (ref "H8") (pin "3") (pinfunction "3_3") (pintype "passive"))
      (node (ref "R8") (pin "1") (pinfunction "1_1") (pintype "passive"))
    )
    (net (code "30") (name "Net-(C29-Pad1)") (class "Default")
      (node (ref "C29") (pin "1") (pinfunction "1_1") (pintype "passive"))
      (node (ref "C9") (pin "2") (pinfunction "2_2") (pintype "passive"))
      (node (ref "H9") (pin "3") (pinfunction "3_3") (pintype "passive"))
      (node (ref "R9") (pin "1") (pinfunction "1_1") (pintype "passive"))
    )
  )
)
